# amplificadorAudio.net
KiCad netlist of a schematic drawn in Altium Designer
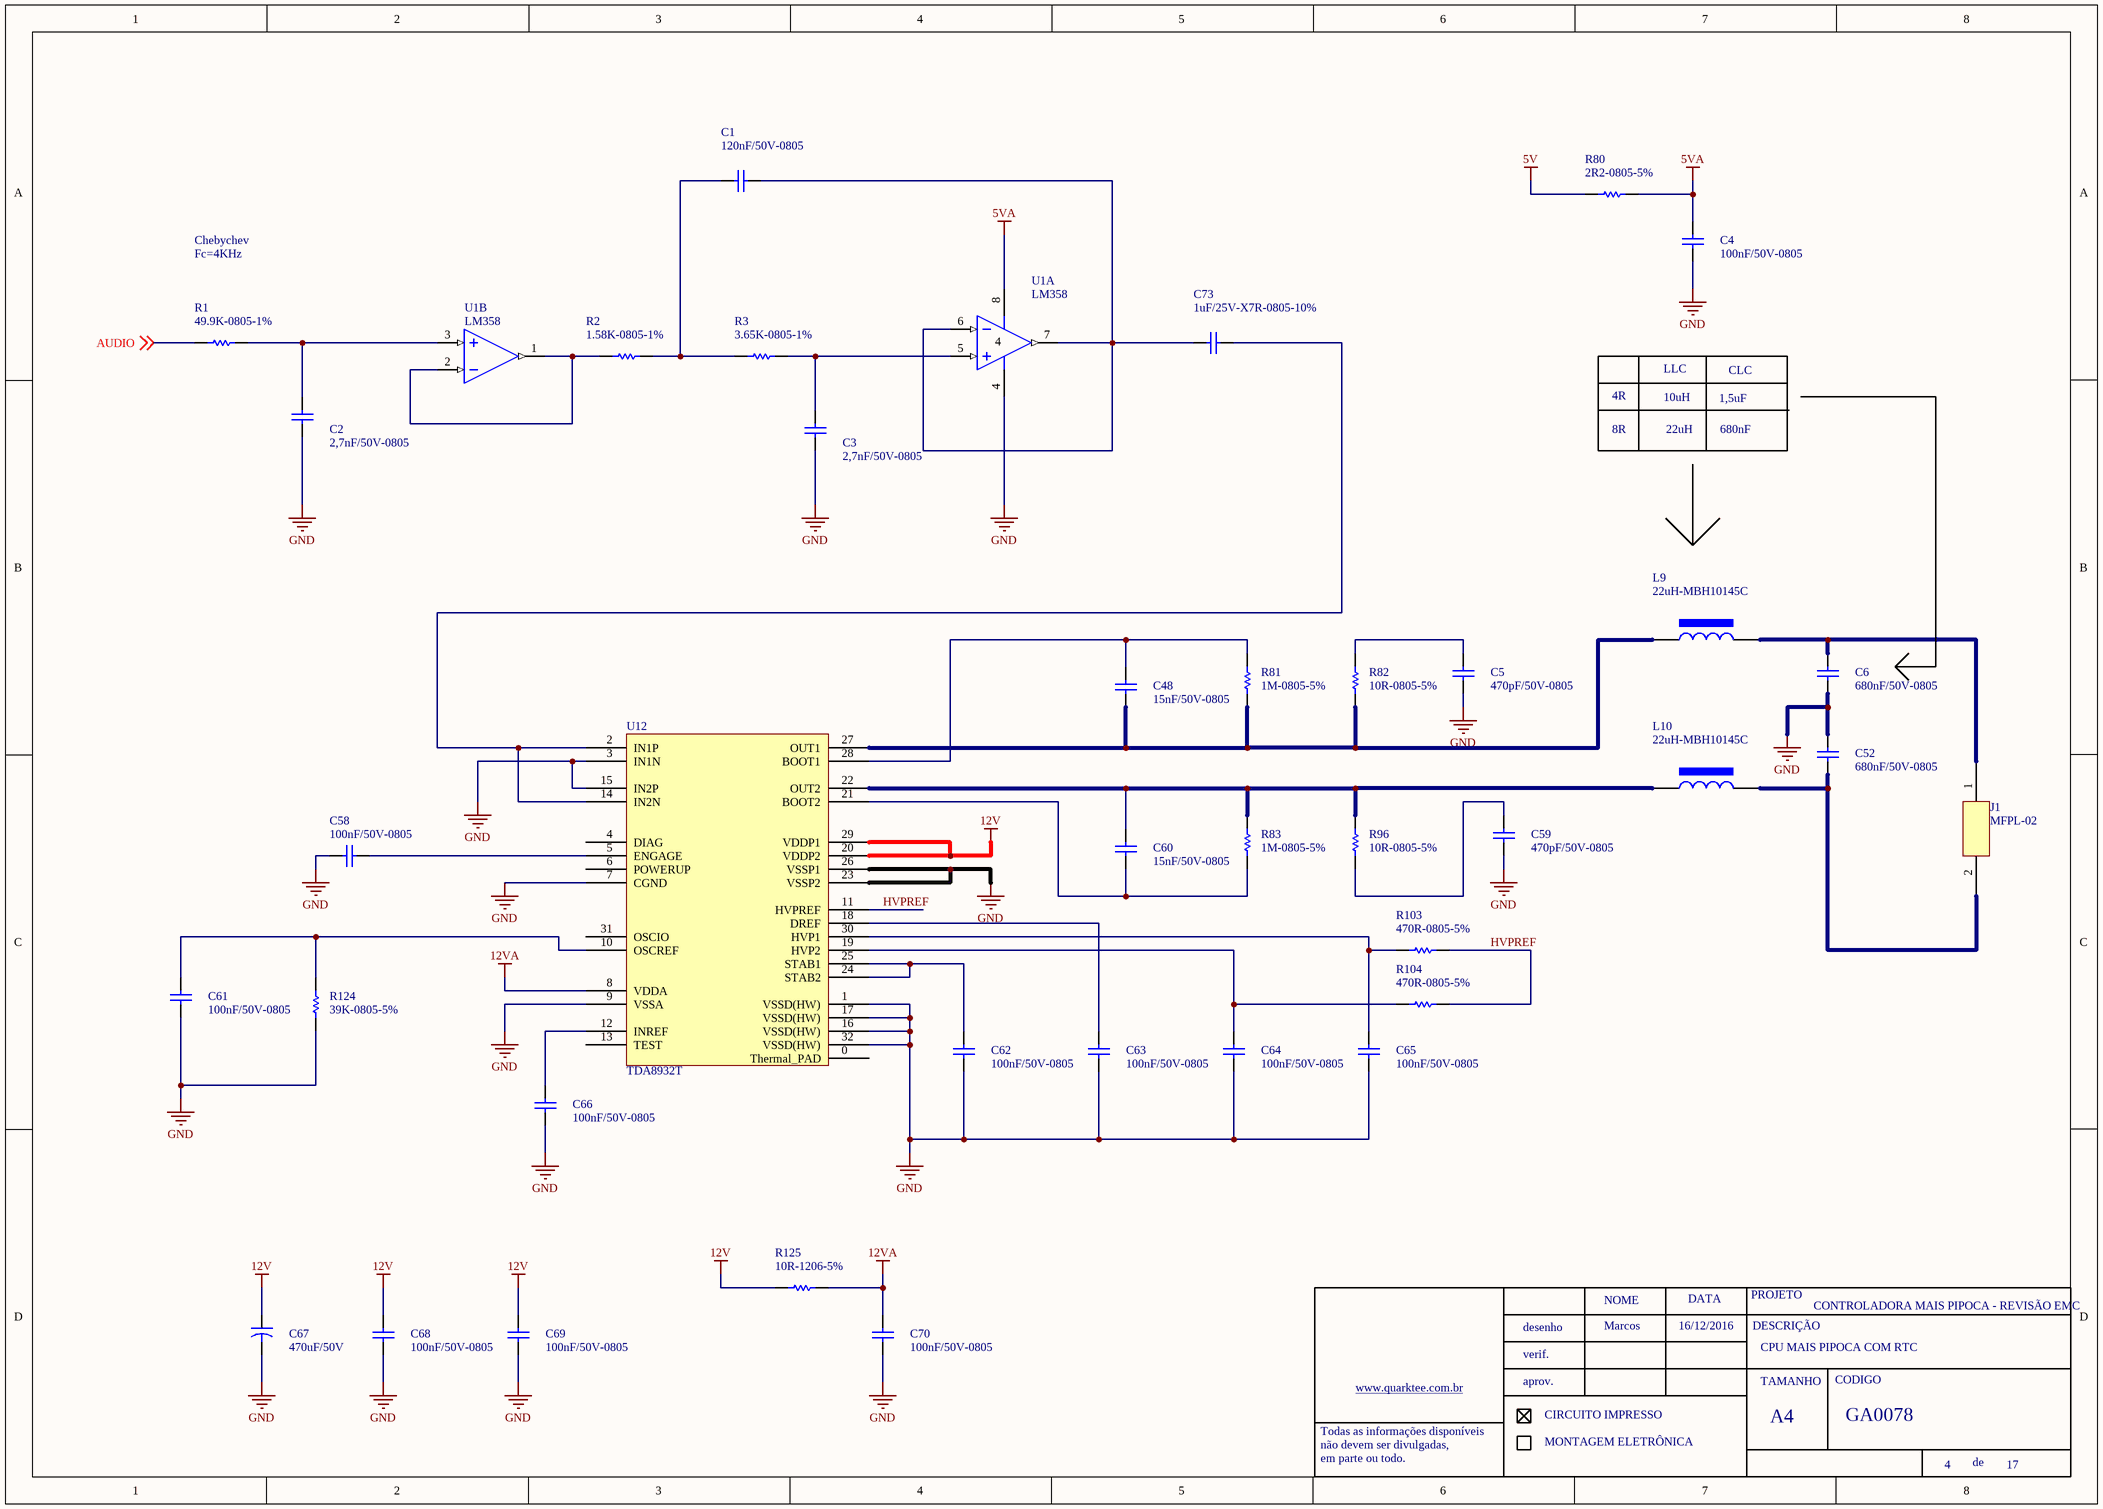
[diagram p0: amplificadorAudio.SchDoc]

(export (version "E")
  (design (tool "Eeschema 10.0.6"))
  (components
    (comp (ref "C1")
      (value "120nF/50V-0805")
      (footprint "0805-REVISADO ONDA")
      (description "100nF/50V-0805")
      (libsource (lib "AquinoLib") (part "100nF/50-0805-NPO"))
    )
    (comp (ref "C2")
      (value "2,7nF/50V-0805")
      (footprint "0805-REVISADO ONDA")
      (description "100nF/50V-0805")
      (libsource (lib "AquinoLib") (part "100nF/50-0805-NPO"))
    )
    (comp (ref "C3")
      (value "2,7nF/50V-0805")
      (footprint "0805-REVISADO ONDA")
      (description "100nF/50V-0805")
      (libsource (lib "AquinoLib") (part "100nF/50-0805-NPO"))
    )
    (comp (ref "C4")
      (value "100nF/50V-0805")
      (footprint "0805-REVISADO ONDA")
      (libsource (lib "AquinoLib") (part "100nF/50-0805-NPO"))
    )
    (comp (ref "C5")
      (value "470pF/50V-0805")
      (footprint "0805-REVISADO ONDA")
      (description "100nF/50V-0805")
      (libsource (lib "AquinoLib") (part "100nF/50-0805-NPO"))
    )
    (comp (ref "C6")
      (value "680nF/50V-0805")
      (footprint "0805-REVISADO ONDA")
      (description "100nF/50V-0805")
      (libsource (lib "AquinoLib") (part "100nF/50-0805-NPO"))
    )
    (comp (ref "C48")
      (value "15nF/50V-0805")
      (footprint "0805-REVISADO ONDA")
      (description "100nF/50V-0805")
      (libsource (lib "AquinoLib") (part "100nF/50-0805-NPO"))
    )
    (comp (ref "C52")
      (value "680nF/50V-0805")
      (footprint "0805-REVISADO ONDA")
      (description "100nF/50V-0805")
      (libsource (lib "AquinoLib") (part "100nF/50-0805-NPO"))
    )
    (comp (ref "C58")
      (value "100nF/50V-0805")
      (footprint "0805-REVISADO ONDA")
      (libsource (lib "AquinoLib") (part "100nF/50-0805-NPO"))
    )
    (comp (ref "C59")
      (value "470pF/50V-0805")
      (footprint "0805-REVISADO ONDA")
      (description "100nF/50V-0805")
      (libsource (lib "AquinoLib") (part "100nF/50-0805-NPO"))
    )
    (comp (ref "C60")
      (value "15nF/50V-0805")
      (footprint "0805-REVISADO ONDA")
      (description "100nF/50V-0805")
      (libsource (lib "AquinoLib") (part "100nF/50-0805-NPO"))
    )
    (comp (ref "C61")
      (value "100nF/50V-0805")
      (footprint "0805-REVISADO ONDA")
      (libsource (lib "AquinoLib") (part "100nF/50-0805-NPO"))
    )
    (comp (ref "C62")
      (value "100nF/50V-0805")
      (footprint "0805-REVISADO ONDA")
      (libsource (lib "AquinoLib") (part "100nF/50-0805-NPO"))
    )
    (comp (ref "C63")
      (value "100nF/50V-0805")
      (footprint "0805-REVISADO ONDA")
      (libsource (lib "AquinoLib") (part "100nF/50-0805-NPO"))
    )
    (comp (ref "C64")
      (value "100nF/50V-0805")
      (footprint "0805-REVISADO ONDA")
      (libsource (lib "AquinoLib") (part "100nF/50-0805-NPO"))
    )
    (comp (ref "C65")
      (value "100nF/50V-0805")
      (footprint "0805-REVISADO ONDA")
      (libsource (lib "AquinoLib") (part "100nF/50-0805-NPO"))
    )
    (comp (ref "C66")
      (value "100nF/50V-0805")
      (footprint "0805-REVISADO ONDA")
      (libsource (lib "AquinoLib") (part "100nF/50-0805-NPO"))
    )
    (comp (ref "C67") (value "470uF/50V") (libsource (lib "AquinoLib") (part "470uF/50V")))
    (comp (ref "C68")
      (value "100nF/50V-0805")
      (footprint "0805-REVISADO ONDA")
      (libsource (lib "AquinoLib") (part "100nF/50-0805-NPO"))
    )
    (comp (ref "C69")
      (value "100nF/50V-0805")
      (footprint "0805-REVISADO ONDA")
      (libsource (lib "AquinoLib") (part "100nF/50-0805-NPO"))
    )
    (comp (ref "C70")
      (value "100nF/50V-0805")
      (footprint "0805-REVISADO ONDA")
      (libsource (lib "AquinoLib") (part "100nF/50-0805-NPO"))
    )
    (comp (ref "C73")
      (value "1uF/25V-X7R-0805-10%")
      (footprint "0805-REVISADO ONDA")
      (description "100nF/50V-0805")
      (libsource (lib "AquinoLib") (part "100nF/50-0805-NPO"))
    )
    (comp (ref "J1") (value "MFPL-02") (footprint "MFPL-02") (libsource (lib "AquinoLib") (part "MFPL-02")))
    (comp (ref "L9")
      (value "22uH-MBH10145C")
      (description "1mH-CNF15-26 AWG")
      (libsource (lib "AquinoLib") (part "indutor 1mH CNF15"))
    )
    (comp (ref "L10")
      (value "22uH-MBH10145C")
      (description "1mH-CNF15-26 AWG")
      (libsource (lib "AquinoLib") (part "indutor 1mH CNF15"))
    )
    (comp (ref "R1")
      (value "49.9K-0805-1%")
      (footprint "0805-REVISADO ONDA")
      (description "10K-0805-5%")
      (libsource (lib "AquinoLib") (part "10K-0805-5%"))
    )
    (comp (ref "R2")
      (value "1.58K-0805-1%")
      (footprint "0805-REVISADO ONDA")
      (description "10K-0805-5%")
      (libsource (lib "AquinoLib") (part "10K-0805-5%"))
    )
    (comp (ref "R3")
      (value "3.65K-0805-1%")
      (footprint "0805-REVISADO ONDA")
      (description "10K-0805-5%")
      (libsource (lib "AquinoLib") (part "10K-0805-5%"))
    )
    (comp (ref "R80")
      (value "2R2-0805-5%")
      (description "10R-0805-5%")
      (libsource (lib "AquinoLib") (part "10R-0805-5%"))
    )
    (comp (ref "R81")
      (value "1M-0805-5%")
      (footprint "0805-REVISADO ONDA")
      (description "10K-0805-5%")
      (libsource (lib "AquinoLib") (part "10K-0805-5%"))
    )
    (comp (ref "R82")
      (value "10R-0805-5%")
      (footprint "0805-REVISADO ONDA")
      (description "10K-0805-5%")
      (libsource (lib "AquinoLib") (part "10K-0805-5%"))
    )
    (comp (ref "R83")
      (value "1M-0805-5%")
      (footprint "0805-REVISADO ONDA")
      (description "10K-0805-5%")
      (libsource (lib "AquinoLib") (part "10K-0805-5%"))
    )
    (comp (ref "R96")
      (value "10R-0805-5%")
      (footprint "0805-REVISADO ONDA")
      (description "10K-0805-5%")
      (libsource (lib "AquinoLib") (part "10K-0805-5%"))
    )
    (comp (ref "R103")
      (value "470R-0805-5%")
      (footprint "0805-REVISADO ONDA")
      (description "10K-0805-5%")
      (libsource (lib "AquinoLib") (part "10K-0805-5%"))
    )
    (comp (ref "R104")
      (value "470R-0805-5%")
      (footprint "0805-REVISADO ONDA")
      (description "10K-0805-5%")
      (libsource (lib "AquinoLib") (part "10K-0805-5%"))
    )
    (comp (ref "R124")
      (value "39K-0805-5%")
      (footprint "0805-REVISADO ONDA")
      (description "10K-0805-5%")
      (libsource (lib "AquinoLib") (part "10K-0805-5%"))
    )
    (comp (ref "R125")
      (value "10R-1206-5%")
      (description "10R-0805-5%")
      (libsource (lib "AquinoLib") (part "10R-0805-5%"))
    )
    (comp (ref "U1") (value "LM358") (libsource (lib "AquinoLib") (part "LM358")))
    (comp (ref "U12") (value "TDA8932T") (libsource (lib "AquinoLib") (part "TDA8932T")))
  )
  (nets
    (net (code "1") (name "/HVPREF") (class "Default")
      (node (ref "R103") (pin "1") (pinfunction "1_1") (pintype "passive"))
      (node (ref "R104") (pin "1") (pinfunction "1_1") (pintype "passive"))
      (node (ref "U12") (pin "11") (pinfunction "HVPREF_11") (pintype "passive"))
    )
    (net (code "2") (name "5V") (class "Default")
      (node (ref "R80") (pin "1") (pinfunction "1_1") (pintype "passive"))
    )
    (net (code "3") (name "5VA") (class "Default")
      (node (ref "C4") (pin "2") (pinfunction "2_2") (pintype "passive"))
      (node (ref "R80") (pin "2") (pinfunction "2_2") (pintype "passive"))
      (node (ref "U1") (pin "8") (pinfunction "V+_8") (pintype "power_in"))
    )
    (net (code "4") (name "12V") (class "Default")
      (node (ref "C67") (pin "1") (pinfunction "1_1") (pintype "passive"))
      (node (ref "C68") (pin "2") (pinfunction "2_2") (pintype "passive"))
      (node (ref "C69") (pin "2") (pinfunction "2_2") (pintype "passive"))
      (node (ref "R125") (pin "1") (pinfunction "1_1") (pintype "passive"))
      (node (ref "U12") (pin "20") (pinfunction "VDDP2_20") (pintype "passive"))
      (node (ref "U12") (pin "29") (pinfunction "VDDP1_29") (pintype "passive"))
    )
    (net (code "5") (name "12VA") (class "Default")
      (node (ref "C70") (pin "2") (pinfunction "2_2") (pintype "passive"))
      (node (ref "R125") (pin "2") (pinfunction "2_2") (pintype "passive"))
      (node (ref "U12") (pin "8") (pinfunction "VDDA_8") (pintype "passive"))
    )
    (net (code "6") (name "AUDIO") (class "Default")
      (node (ref "R1") (pin "1") (pinfunction "1_1") (pintype "passive"))
    )
    (net (code "7") (name "GND") (class "Default")
      (node (ref "C2") (pin "1") (pinfunction "1_1") (pintype "passive"))
      (node (ref "C3") (pin "1") (pinfunction "1_1") (pintype "passive"))
      (node (ref "C4") (pin "1") (pinfunction "1_1") (pintype "passive"))
      (node (ref "C5") (pin "1") (pinfunction "1_1") (pintype "passive"))
      (node (ref "C52") (pin "2") (pinfunction "2_2") (pintype "passive"))
      (node (ref "C58") (pin "2") (pinfunction "2_2") (pintype "passive"))
      (node (ref "C59") (pin "1") (pinfunction "1_1") (pintype "passive"))
      (node (ref "C6") (pin "1") (pinfunction "1_1") (pintype "passive"))
      (node (ref "C61") (pin "1") (pinfunction "1_1") (pintype "passive"))
      (node (ref "C62") (pin "1") (pinfunction "1_1") (pintype "passive"))
      (node (ref "C63") (pin "1") (pinfunction "1_1") (pintype "passive"))
      (node (ref "C64") (pin "1") (pinfunction "1_1") (pintype "passive"))
      (node (ref "C65") (pin "1") (pinfunction "1_1") (pintype "passive"))
      (node (ref "C66") (pin "1") (pinfunction "1_1") (pintype "passive"))
      (node (ref "C67") (pin "2") (pinfunction "2_2") (pintype "passive"))
      (node (ref "C68") (pin "1") (pinfunction "1_1") (pintype "passive"))
      (node (ref "C69") (pin "1") (pinfunction "1_1") (pintype "passive"))
      (node (ref "C70") (pin "1") (pinfunction "1_1") (pintype "passive"))
      (node (ref "R124") (pin "1") (pinfunction "1_1") (pintype "passive"))
      (node (ref "U1") (pin "4") (pinfunction "GND_4") (pintype "power_in"))
      (node (ref "U12") (pin "1") (pinfunction "VSSD(HW)_1") (pintype "passive"))
      (node (ref "U12") (pin "15") (pinfunction "IN2P_15") (pintype "passive"))
      (node (ref "U12") (pin "16") (pinfunction "VSSD(HW)_16") (pintype "passive"))
      (node (ref "U12") (pin "17") (pinfunction "VSSD(HW)_17") (pintype "passive"))
      (node (ref "U12") (pin "23") (pinfunction "VSSP2_23") (pintype "passive"))
      (node (ref "U12") (pin "26") (pinfunction "VSSP1_26") (pintype "passive"))
      (node (ref "U12") (pin "3") (pinfunction "IN1N_3") (pintype "passive"))
      (node (ref "U12") (pin "32") (pinfunction "VSSD(HW)_32") (pintype "passive"))
      (node (ref "U12") (pin "7") (pinfunction "CGND_7") (pintype "passive"))
      (node (ref "U12") (pin "9") (pinfunction "VSSA_9") (pintype "passive"))
    )
    (net (code "8") (name "Net-(C1-Pad2)") (class "Default")
      (node (ref "C1") (pin "2") (pinfunction "2_2") (pintype "passive"))
      (node (ref "R2") (pin "2") (pinfunction "2_2") (pintype "passive"))
      (node (ref "R3") (pin "1") (pinfunction "1_1") (pintype "passive"))
    )
    (net (code "9") (name "Net-(C5-Pad2)") (class "Default")
      (node (ref "C5") (pin "2") (pinfunction "2_2") (pintype "passive"))
      (node (ref "R82") (pin "1") (pinfunction "1_1") (pintype "passive"))
    )
    (net (code "10") (name "Net-(C6-Pad2)") (class "Default")
      (node (ref "C6") (pin "2") (pinfunction "2_2") (pintype "passive"))
      (node (ref "J1") (pin "1") (pinfunction "1_1") (pintype "passive"))
      (node (ref "L9") (pin "1") (pinfunction "1_1") (pintype "passive"))
    )
    (net (code "11") (name "Net-(C52-Pad1)") (class "Default")
      (node (ref "C52") (pin "1") (pinfunction "1_1") (pintype "passive"))
      (node (ref "J1") (pin "2") (pinfunction "2_2") (pintype "passive"))
      (node (ref "L10") (pin "1") (pinfunction "1_1") (pintype "passive"))
    )
    (net (code "12") (name "Net-(C59-Pad2)") (class "Default")
      (node (ref "C59") (pin "2") (pinfunction "2_2") (pintype "passive"))
      (node (ref "R96") (pin "2") (pinfunction "2_2") (pintype "passive"))
    )
    (net (code "13") (name "Net-(U1A-IN+)") (class "Default")
      (node (ref "C3") (pin "2") (pinfunction "2_2") (pintype "passive"))
      (node (ref "R3") (pin "2") (pinfunction "2_2") (pintype "passive"))
      (node (ref "U1") (pin "5") (pinfunction "IN+_5") (pintype "input"))
    )
    (net (code "14") (name "Net-(U1A-IN-)") (class "Default")
      (node (ref "C1") (pin "1") (pinfunction "1_1") (pintype "passive"))
      (node (ref "C73") (pin "2") (pinfunction "2_2") (pintype "passive"))
      (node (ref "U1") (pin "6") (pinfunction "IN-_6") (pintype "input"))
      (node (ref "U1") (pin "7") (pinfunction "OUT_7") (pintype "output"))
    )
    (net (code "15") (name "Net-(U1B-IN+)") (class "Default")
      (node (ref "C2") (pin "2") (pinfunction "2_2") (pintype "passive"))
      (node (ref "R1") (pin "2") (pinfunction "2_2") (pintype "passive"))
      (node (ref "U1") (pin "3") (pinfunction "IN+_3") (pintype "input"))
    )
    (net (code "16") (name "Net-(U1B-IN-)") (class "Default")
      (node (ref "R2") (pin "1") (pinfunction "1_1") (pintype "passive"))
      (node (ref "U1") (pin "1") (pinfunction "OUT_1") (pintype "output"))
      (node (ref "U1") (pin "2") (pinfunction "IN-_2") (pintype "input"))
    )
    (net (code "17") (name "Net-(U12-BOOT1)") (class "Default")
      (node (ref "C48") (pin "2") (pinfunction "2_2") (pintype "passive"))
      (node (ref "R81") (pin "1") (pinfunction "1_1") (pintype "passive"))
      (node (ref "U12") (pin "28") (pinfunction "BOOT1_28") (pintype "passive"))
    )
    (net (code "18") (name "Net-(U12-BOOT2)") (class "Default")
      (node (ref "C60") (pin "1") (pinfunction "1_1") (pintype "passive"))
      (node (ref "R83") (pin "2") (pinfunction "2_2") (pintype "passive"))
      (node (ref "U12") (pin "21") (pinfunction "BOOT2_21") (pintype "passive"))
    )
    (net (code "19") (name "Net-(U12-DREF)") (class "Default")
      (node (ref "C63") (pin "2") (pinfunction "2_2") (pintype "passive"))
      (node (ref "U12") (pin "18") (pinfunction "DREF_18") (pintype "passive"))
    )
    (net (code "20") (name "Net-(U12-ENGAGE)") (class "Default")
      (node (ref "C58") (pin "1") (pinfunction "1_1") (pintype "passive"))
      (node (ref "U12") (pin "5") (pinfunction "ENGAGE_5") (pintype "passive"))
    )
    (net (code "21") (name "Net-(U12-HVP1)") (class "Default")
      (node (ref "C65") (pin "2") (pinfunction "2_2") (pintype "passive"))
      (node (ref "R103") (pin "2") (pinfunction "2_2") (pintype "passive"))
      (node (ref "U12") (pin "30") (pinfunction "HVP1_30") (pintype "passive"))
    )
    (net (code "22") (name "Net-(U12-HVP2)") (class "Default")
      (node (ref "C64") (pin "2") (pinfunction "2_2") (pintype "passive"))
      (node (ref "R104") (pin "2") (pinfunction "2_2") (pintype "passive"))
      (node (ref "U12") (pin "19") (pinfunction "HVP2_19") (pintype "passive"))
    )
    (net (code "23") (name "Net-(U12-IN1P)") (class "Default")
      (node (ref "C73") (pin "1") (pinfunction "1_1") (pintype "passive"))
      (node (ref "U12") (pin "14") (pinfunction "IN2N_14") (pintype "passive"))
      (node (ref "U12") (pin "2") (pinfunction "IN1P_2") (pintype "passive"))
    )
    (net (code "24") (name "Net-(U12-INREF)") (class "Default")
      (node (ref "C66") (pin "2") (pinfunction "2_2") (pintype "passive"))
      (node (ref "U12") (pin "12") (pinfunction "INREF_12") (pintype "passive"))
    )
    (net (code "25") (name "Net-(U12-OSCREF)") (class "Default")
      (node (ref "C61") (pin "2") (pinfunction "2_2") (pintype "passive"))
      (node (ref "R124") (pin "2") (pinfunction "2_2") (pintype "passive"))
      (node (ref "U12") (pin "10") (pinfunction "OSCREF_10") (pintype "passive"))
    )
    (net (code "26") (name "Net-(U12-OUT1)") (class "Default")
      (node (ref "C48") (pin "1") (pinfunction "1_1") (pintype "passive"))
      (node (ref "L9") (pin "2") (pinfunction "2_2") (pintype "passive"))
      (node (ref "R81") (pin "2") (pinfunction "2_2") (pintype "passive"))
      (node (ref "R82") (pin "2") (pinfunction "2_2") (pintype "passive"))
      (node (ref "U12") (pin "27") (pinfunction "OUT1_27") (pintype "passive"))
    )
    (net (code "27") (name "Net-(U12-OUT2)") (class "Default")
      (node (ref "C60") (pin "2") (pinfunction "2_2") (pintype "passive"))
      (node (ref "L10") (pin "2") (pinfunction "2_2") (pintype "passive"))
      (node (ref "R83") (pin "1") (pinfunction "1_1") (pintype "passive"))
      (node (ref "R96") (pin "1") (pinfunction "1_1") (pintype "passive"))
      (node (ref "U12") (pin "22") (pinfunction "OUT2_22") (pintype "passive"))
    )
    (net (code "28") (name "Net-(U12-STAB1)") (class "Default")
      (node (ref "C62") (pin "2") (pinfunction "2_2") (pintype "passive"))
      (node (ref "U12") (pin "24") (pinfunction "STAB2_24") (pintype "passive"))
      (node (ref "U12") (pin "25") (pinfunction "STAB1_25") (pintype "passive"))
    )
    (net (code "29") (name "unconnected-(U12-DIAG-Pad4)") (class "Default")
      (node (ref "U12") (pin "4") (pinfunction "DIAG_4") (pintype "passive"))
    )
    (net (code "30") (name "unconnected-(U12-OSCIO-Pad31)") (class "Default")
      (node (ref "U12") (pin "31") (pinfunction "OSCIO_31") (pintype "passive"))
    )
    (net (code "31") (name "unconnected-(U12-POWERUP-Pad6)") (class "Default")
      (node (ref "U12") (pin "6") (pinfunction "POWERUP_6") (pintype "passive"))
    )
    (net (code "32") (name "unconnected-(U12-TEST-Pad13)") (class "Default")
      (node (ref "U12") (pin "13") (pinfunction "TEST_13") (pintype "passive"))
    )
    (net (code "33") (name "unconnected-(U12-Thermal_PAD-Pad0)") (class "Default")
      (node (ref "U12") (pin "0") (pinfunction "Thermal_PAD_0") (pintype "passive"))
    )
  )
)
